# Connectors.net
KiCad netlist of a schematic drawn in Altium Designer
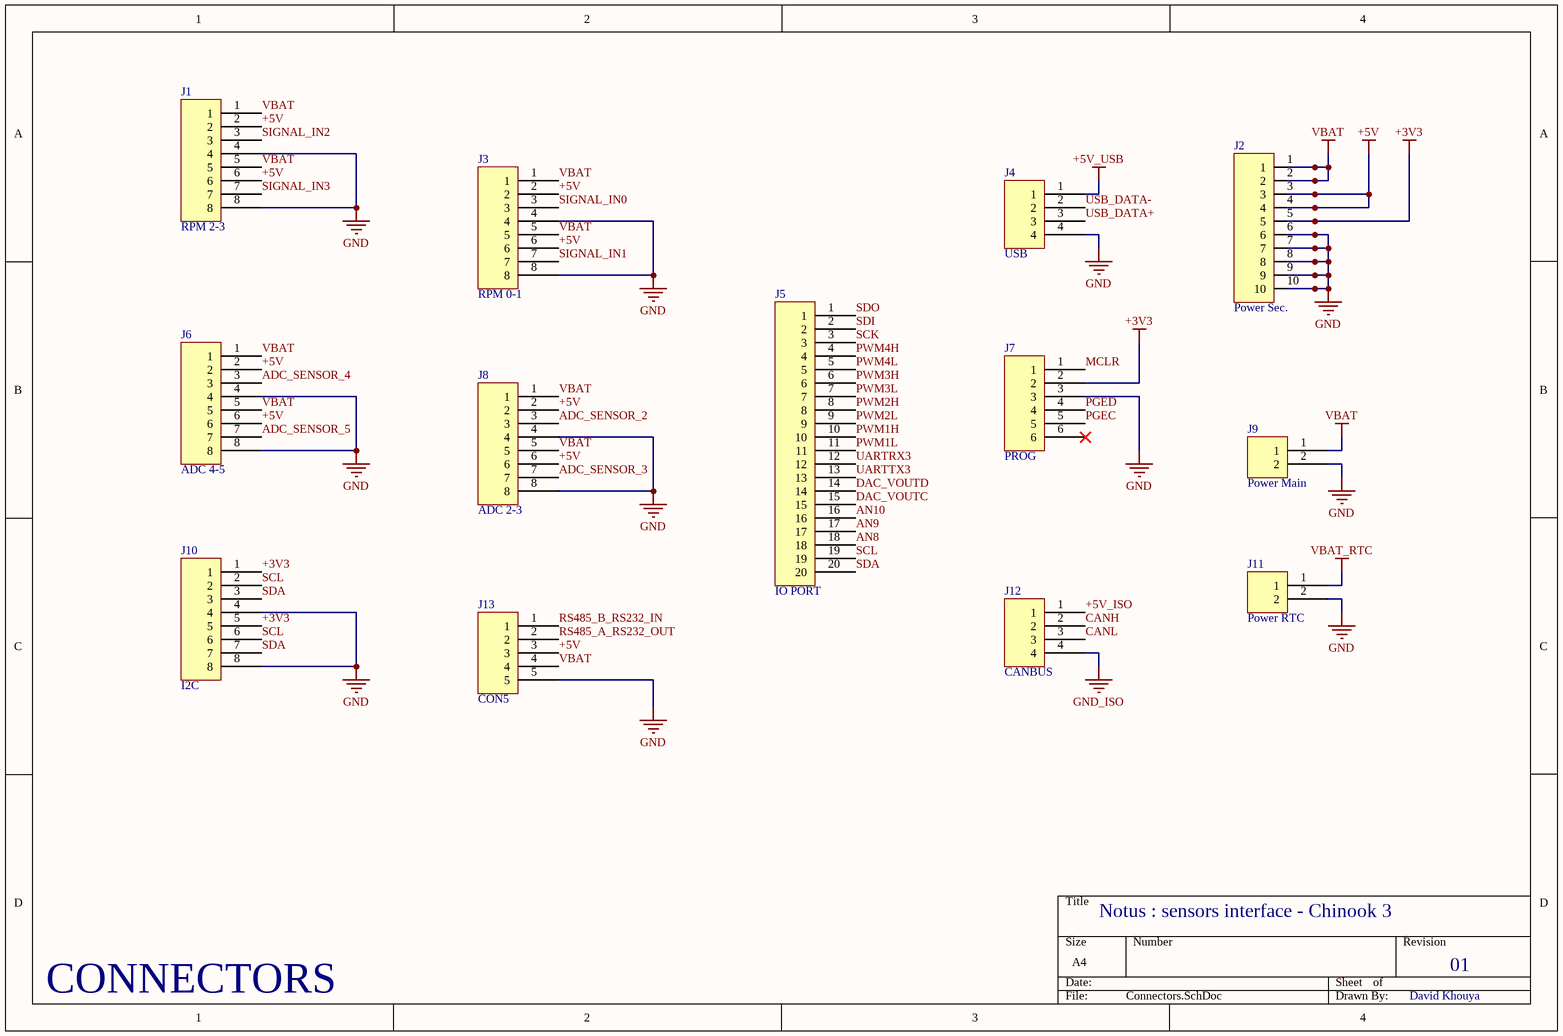
[diagram p0: Connectors.SchDoc]

(export (version "E")
  (design (tool "Eeschema 10.0.6"))
  (components
    (comp (ref "J1")
      (value "RPM 2-3")
      (footprint "1633600000")
      (description "8 pins connector")
      (libsource (lib "dkhouya") (part "CON8"))
    )
    (comp (ref "J2")
      (value "Power Sec.")
      (footprint "104652-1")
      (description "10 pins connector")
      (libsource (lib "dkhouya") (part "CON10"))
    )
    (comp (ref "J3")
      (value "RPM 0-1")
      (footprint "1633600000")
      (description "8 pins connector")
      (libsource (lib "dkhouya") (part "CON8"))
    )
    (comp (ref "J4")
      (value "USB")
      (footprint "AU-Y1007-R")
      (description "4 pins connector")
      (libsource (lib "dkhouya") (part "CON4"))
    )
    (comp (ref "J5")
      (value "IO PORT")
      (footprint "104652-2")
      (description "20 pins connector")
      (libsource (lib "dkhouya") (part "CON20"))
    )
    (comp (ref "J6")
      (value "ADC 4-5")
      (footprint "1633600000")
      (description "8 pins connector")
      (libsource (lib "dkhouya") (part "CON8"))
    )
    (comp (ref "J7")
      (value "PROG")
      (footprint "A31411-ND")
      (description "6 pins connectors")
      (libsource (lib "dkhouya") (part "CON6"))
    )
    (comp (ref "J8")
      (value "ADC 2-3")
      (footprint "1633600000")
      (description "8 pins connector")
      (libsource (lib "dkhouya") (part "CON8"))
    )
    (comp (ref "J9")
      (value "Power Main")
      (footprint "XT60_CON")
      (description "2 pins connector")
      (libsource (lib "dkhouya") (part "CON2"))
    )
    (comp (ref "J10")
      (value "I2C")
      (footprint "1633600000")
      (description "8 pins connector")
      (libsource (lib "dkhouya") (part "CON8"))
    )
    (comp (ref "J11")
      (value "Power RTC")
      (footprint "BS-1225-PC")
      (description "2 pins connector")
      (libsource (lib "dkhouya") (part "CON2"))
    )
    (comp (ref "J12")
      (value "CANBUS")
      (footprint "con4_200mils")
      (description "4 pins connector")
      (libsource (lib "dkhouya") (part "CON4"))
    )
    (comp (ref "J13")
      (value "CON5")
      (footprint "1607070000")
      (description "5 pins connector")
      (libsource (lib "dkhouya") (part "CON5"))
    )
  )
  (nets
    (net (code "1") (name "+3V3") (class "Default")
      (node (ref "J10") (pin "1") (pinfunction "1_1") (pintype "passive"))
      (node (ref "J10") (pin "5") (pinfunction "5_5") (pintype "passive"))
      (node (ref "J2") (pin "5") (pinfunction "5_5") (pintype "passive"))
      (node (ref "J7") (pin "2") (pinfunction "2_2") (pintype "passive"))
    )
    (net (code "2") (name "+5V") (class "Default")
      (node (ref "J1") (pin "2") (pinfunction "2_2") (pintype "passive"))
      (node (ref "J1") (pin "6") (pinfunction "6_6") (pintype "passive"))
      (node (ref "J13") (pin "3") (pinfunction "3_3") (pintype "passive"))
      (node (ref "J2") (pin "3") (pinfunction "3_3") (pintype "passive"))
      (node (ref "J2") (pin "4") (pinfunction "4_4") (pintype "passive"))
      (node (ref "J3") (pin "2") (pinfunction "2_2") (pintype "passive"))
      (node (ref "J3") (pin "6") (pinfunction "6_6") (pintype "passive"))
      (node (ref "J6") (pin "2") (pinfunction "2_2") (pintype "passive"))
      (node (ref "J6") (pin "6") (pinfunction "6_6") (pintype "passive"))
      (node (ref "J8") (pin "2") (pinfunction "2_2") (pintype "passive"))
      (node (ref "J8") (pin "6") (pinfunction "6_6") (pintype "passive"))
    )
    (net (code "3") (name "+5V_USB") (class "Default")
      (node (ref "J4") (pin "1") (pinfunction "1_1") (pintype "passive"))
    )
    (net (code "4") (name "/+5V_ISO") (class "Default")
      (node (ref "J12") (pin "1") (pinfunction "1_1") (pintype "passive"))
    )
    (net (code "5") (name "/ADC_SENSOR_2") (class "Default")
      (node (ref "J8") (pin "3") (pinfunction "3_3") (pintype "passive"))
    )
    (net (code "6") (name "/ADC_SENSOR_3") (class "Default")
      (node (ref "J8") (pin "7") (pinfunction "7_7") (pintype "passive"))
    )
    (net (code "7") (name "/ADC_SENSOR_4") (class "Default")
      (node (ref "J6") (pin "3") (pinfunction "3_3") (pintype "passive"))
    )
    (net (code "8") (name "/ADC_SENSOR_5") (class "Default")
      (node (ref "J6") (pin "7") (pinfunction "7_7") (pintype "passive"))
    )
    (net (code "9") (name "/AN8") (class "Default")
      (node (ref "J5") (pin "18") (pinfunction "18_18") (pintype "passive"))
    )
    (net (code "10") (name "/AN9") (class "Default")
      (node (ref "J5") (pin "17") (pinfunction "17_17") (pintype "passive"))
    )
    (net (code "11") (name "/AN10") (class "Default")
      (node (ref "J5") (pin "16") (pinfunction "16_16") (pintype "passive"))
    )
    (net (code "12") (name "/CANH") (class "Default")
      (node (ref "J12") (pin "2") (pinfunction "2_2") (pintype "passive"))
    )
    (net (code "13") (name "/CANL") (class "Default")
      (node (ref "J12") (pin "3") (pinfunction "3_3") (pintype "passive"))
    )
    (net (code "14") (name "/DAC_VOUTC") (class "Default")
      (node (ref "J5") (pin "15") (pinfunction "15_15") (pintype "passive"))
    )
    (net (code "15") (name "/DAC_VOUTD") (class "Default")
      (node (ref "J5") (pin "14") (pinfunction "14_14") (pintype "passive"))
    )
    (net (code "16") (name "/MCLR") (class "Default")
      (node (ref "J7") (pin "1") (pinfunction "1_1") (pintype "passive"))
    )
    (net (code "17") (name "/PGEC") (class "Default")
      (node (ref "J7") (pin "5") (pinfunction "5_5") (pintype "passive"))
    )
    (net (code "18") (name "/PGED") (class "Default")
      (node (ref "J7") (pin "4") (pinfunction "4_4") (pintype "passive"))
    )
    (net (code "19") (name "/PWM1H") (class "Default")
      (node (ref "J5") (pin "10") (pinfunction "10_10") (pintype "passive"))
    )
    (net (code "20") (name "/PWM1L") (class "Default")
      (node (ref "J5") (pin "11") (pinfunction "11_11") (pintype "passive"))
    )
    (net (code "21") (name "/PWM2H") (class "Default")
      (node (ref "J5") (pin "8") (pinfunction "8_8") (pintype "passive"))
    )
    (net (code "22") (name "/PWM2L") (class "Default")
      (node (ref "J5") (pin "9") (pinfunction "9_9") (pintype "passive"))
    )
    (net (code "23") (name "/PWM3H") (class "Default")
      (node (ref "J5") (pin "6") (pinfunction "6_6") (pintype "passive"))
    )
    (net (code "24") (name "/PWM3L") (class "Default")
      (node (ref "J5") (pin "7") (pinfunction "7_7") (pintype "passive"))
    )
    (net (code "25") (name "/PWM4H") (class "Default")
      (node (ref "J5") (pin "4") (pinfunction "4_4") (pintype "passive"))
    )
    (net (code "26") (name "/PWM4L") (class "Default")
      (node (ref "J5") (pin "5") (pinfunction "5_5") (pintype "passive"))
    )
    (net (code "27") (name "/RS485_A_RS232_OUT") (class "Default")
      (node (ref "J13") (pin "2") (pinfunction "2_2") (pintype "passive"))
    )
    (net (code "28") (name "/RS485_B_RS232_IN") (class "Default")
      (node (ref "J13") (pin "1") (pinfunction "1_1") (pintype "passive"))
    )
    (net (code "29") (name "/SCK") (class "Default")
      (node (ref "J5") (pin "3") (pinfunction "3_3") (pintype "passive"))
    )
    (net (code "30") (name "/SCL") (class "Default")
      (node (ref "J10") (pin "2") (pinfunction "2_2") (pintype "passive"))
      (node (ref "J10") (pin "6") (pinfunction "6_6") (pintype "passive"))
      (node (ref "J5") (pin "19") (pinfunction "19_19") (pintype "passive"))
    )
    (net (code "31") (name "/SDA") (class "Default")
      (node (ref "J10") (pin "3") (pinfunction "3_3") (pintype "passive"))
      (node (ref "J10") (pin "7") (pinfunction "7_7") (pintype "passive"))
      (node (ref "J5") (pin "20") (pinfunction "20_20") (pintype "passive"))
    )
    (net (code "32") (name "/SDI") (class "Default")
      (node (ref "J5") (pin "2") (pinfunction "2_2") (pintype "passive"))
    )
    (net (code "33") (name "/SDO") (class "Default")
      (node (ref "J5") (pin "1") (pinfunction "1_1") (pintype "passive"))
    )
    (net (code "34") (name "/SIGNAL_IN0") (class "Default")
      (node (ref "J3") (pin "3") (pinfunction "3_3") (pintype "passive"))
    )
    (net (code "35") (name "/SIGNAL_IN1") (class "Default")
      (node (ref "J3") (pin "7") (pinfunction "7_7") (pintype "passive"))
    )
    (net (code "36") (name "/SIGNAL_IN2") (class "Default")
      (node (ref "J1") (pin "3") (pinfunction "3_3") (pintype "passive"))
    )
    (net (code "37") (name "/SIGNAL_IN3") (class "Default")
      (node (ref "J1") (pin "7") (pinfunction "7_7") (pintype "passive"))
    )
    (net (code "38") (name "/UARTRX3") (class "Default")
      (node (ref "J5") (pin "12") (pinfunction "12_12") (pintype "passive"))
    )
    (net (code "39") (name "/UARTTX3") (class "Default")
      (node (ref "J5") (pin "13") (pinfunction "13_13") (pintype "passive"))
    )
    (net (code "40") (name "/USB_DATA+") (class "Default")
      (node (ref "J4") (pin "3") (pinfunction "3_3") (pintype "passive"))
    )
    (net (code "41") (name "/USB_DATA-") (class "Default")
      (node (ref "J4") (pin "2") (pinfunction "2_2") (pintype "passive"))
    )
    (net (code "42") (name "GND") (class "Default")
      (node (ref "J1") (pin "4") (pinfunction "4_4") (pintype "passive"))
      (node (ref "J1") (pin "8") (pinfunction "8_8") (pintype "passive"))
      (node (ref "J10") (pin "4") (pinfunction "4_4") (pintype "passive"))
      (node (ref "J10") (pin "8") (pinfunction "8_8") (pintype "passive"))
      (node (ref "J11") (pin "2") (pinfunction "2_2") (pintype "passive"))
      (node (ref "J13") (pin "5") (pinfunction "5_5") (pintype "passive"))
      (node (ref "J2") (pin "10") (pinfunction "10_10") (pintype "passive"))
      (node (ref "J2") (pin "6") (pinfunction "6_6") (pintype "passive"))
      (node (ref "J2") (pin "7") (pinfunction "7_7") (pintype "passive"))
      (node (ref "J2") (pin "8") (pinfunction "8_8") (pintype "passive"))
      (node (ref "J2") (pin "9") (pinfunction "9_9") (pintype "passive"))
      (node (ref "J3") (pin "4") (pinfunction "4_4") (pintype "passive"))
      (node (ref "J3") (pin "8") (pinfunction "8_8") (pintype "passive"))
      (node (ref "J4") (pin "4") (pinfunction "4_4") (pintype "passive"))
      (node (ref "J6") (pin "4") (pinfunction "4_4") (pintype "passive"))
      (node (ref "J6") (pin "8") (pinfunction "8_8") (pintype "passive"))
      (node (ref "J7") (pin "3") (pinfunction "3_3") (pintype "passive"))
      (node (ref "J8") (pin "4") (pinfunction "4_4") (pintype "passive"))
      (node (ref "J8") (pin "8") (pinfunction "8_8") (pintype "passive"))
      (node (ref "J9") (pin "2") (pinfunction "2_2") (pintype "passive"))
    )
    (net (code "43") (name "GND_ISO") (class "Default")
      (node (ref "J12") (pin "4") (pinfunction "4_4") (pintype "passive"))
    )
    (net (code "44") (name "VBAT") (class "Default")
      (node (ref "J1") (pin "1") (pinfunction "1_1") (pintype "passive"))
      (node (ref "J1") (pin "5") (pinfunction "5_5") (pintype "passive"))
      (node (ref "J13") (pin "4") (pinfunction "4_4") (pintype "passive"))
      (node (ref "J2") (pin "1") (pinfunction "1_1") (pintype "passive"))
      (node (ref "J2") (pin "2") (pinfunction "2_2") (pintype "passive"))
      (node (ref "J3") (pin "1") (pinfunction "1_1") (pintype "passive"))
      (node (ref "J3") (pin "5") (pinfunction "5_5") (pintype "passive"))
      (node (ref "J6") (pin "1") (pinfunction "1_1") (pintype "passive"))
      (node (ref "J6") (pin "5") (pinfunction "5_5") (pintype "passive"))
      (node (ref "J8") (pin "1") (pinfunction "1_1") (pintype "passive"))
      (node (ref "J8") (pin "5") (pinfunction "5_5") (pintype "passive"))
      (node (ref "J9") (pin "1") (pinfunction "1_1") (pintype "passive"))
    )
    (net (code "45") (name "VBAT_RTC") (class "Default")
      (node (ref "J11") (pin "1") (pinfunction "1_1") (pintype "passive"))
    )
    (net (code "46") (name "unconnected-(J7-Pad6)") (class "Default")
      (node (ref "J7") (pin "6") (pinfunction "6_6") (pintype "passive+no_connect"))
    )
  )
)
